# BLM_Badge_rev_B.net
KiCad netlist of a schematic drawn in EAGLE
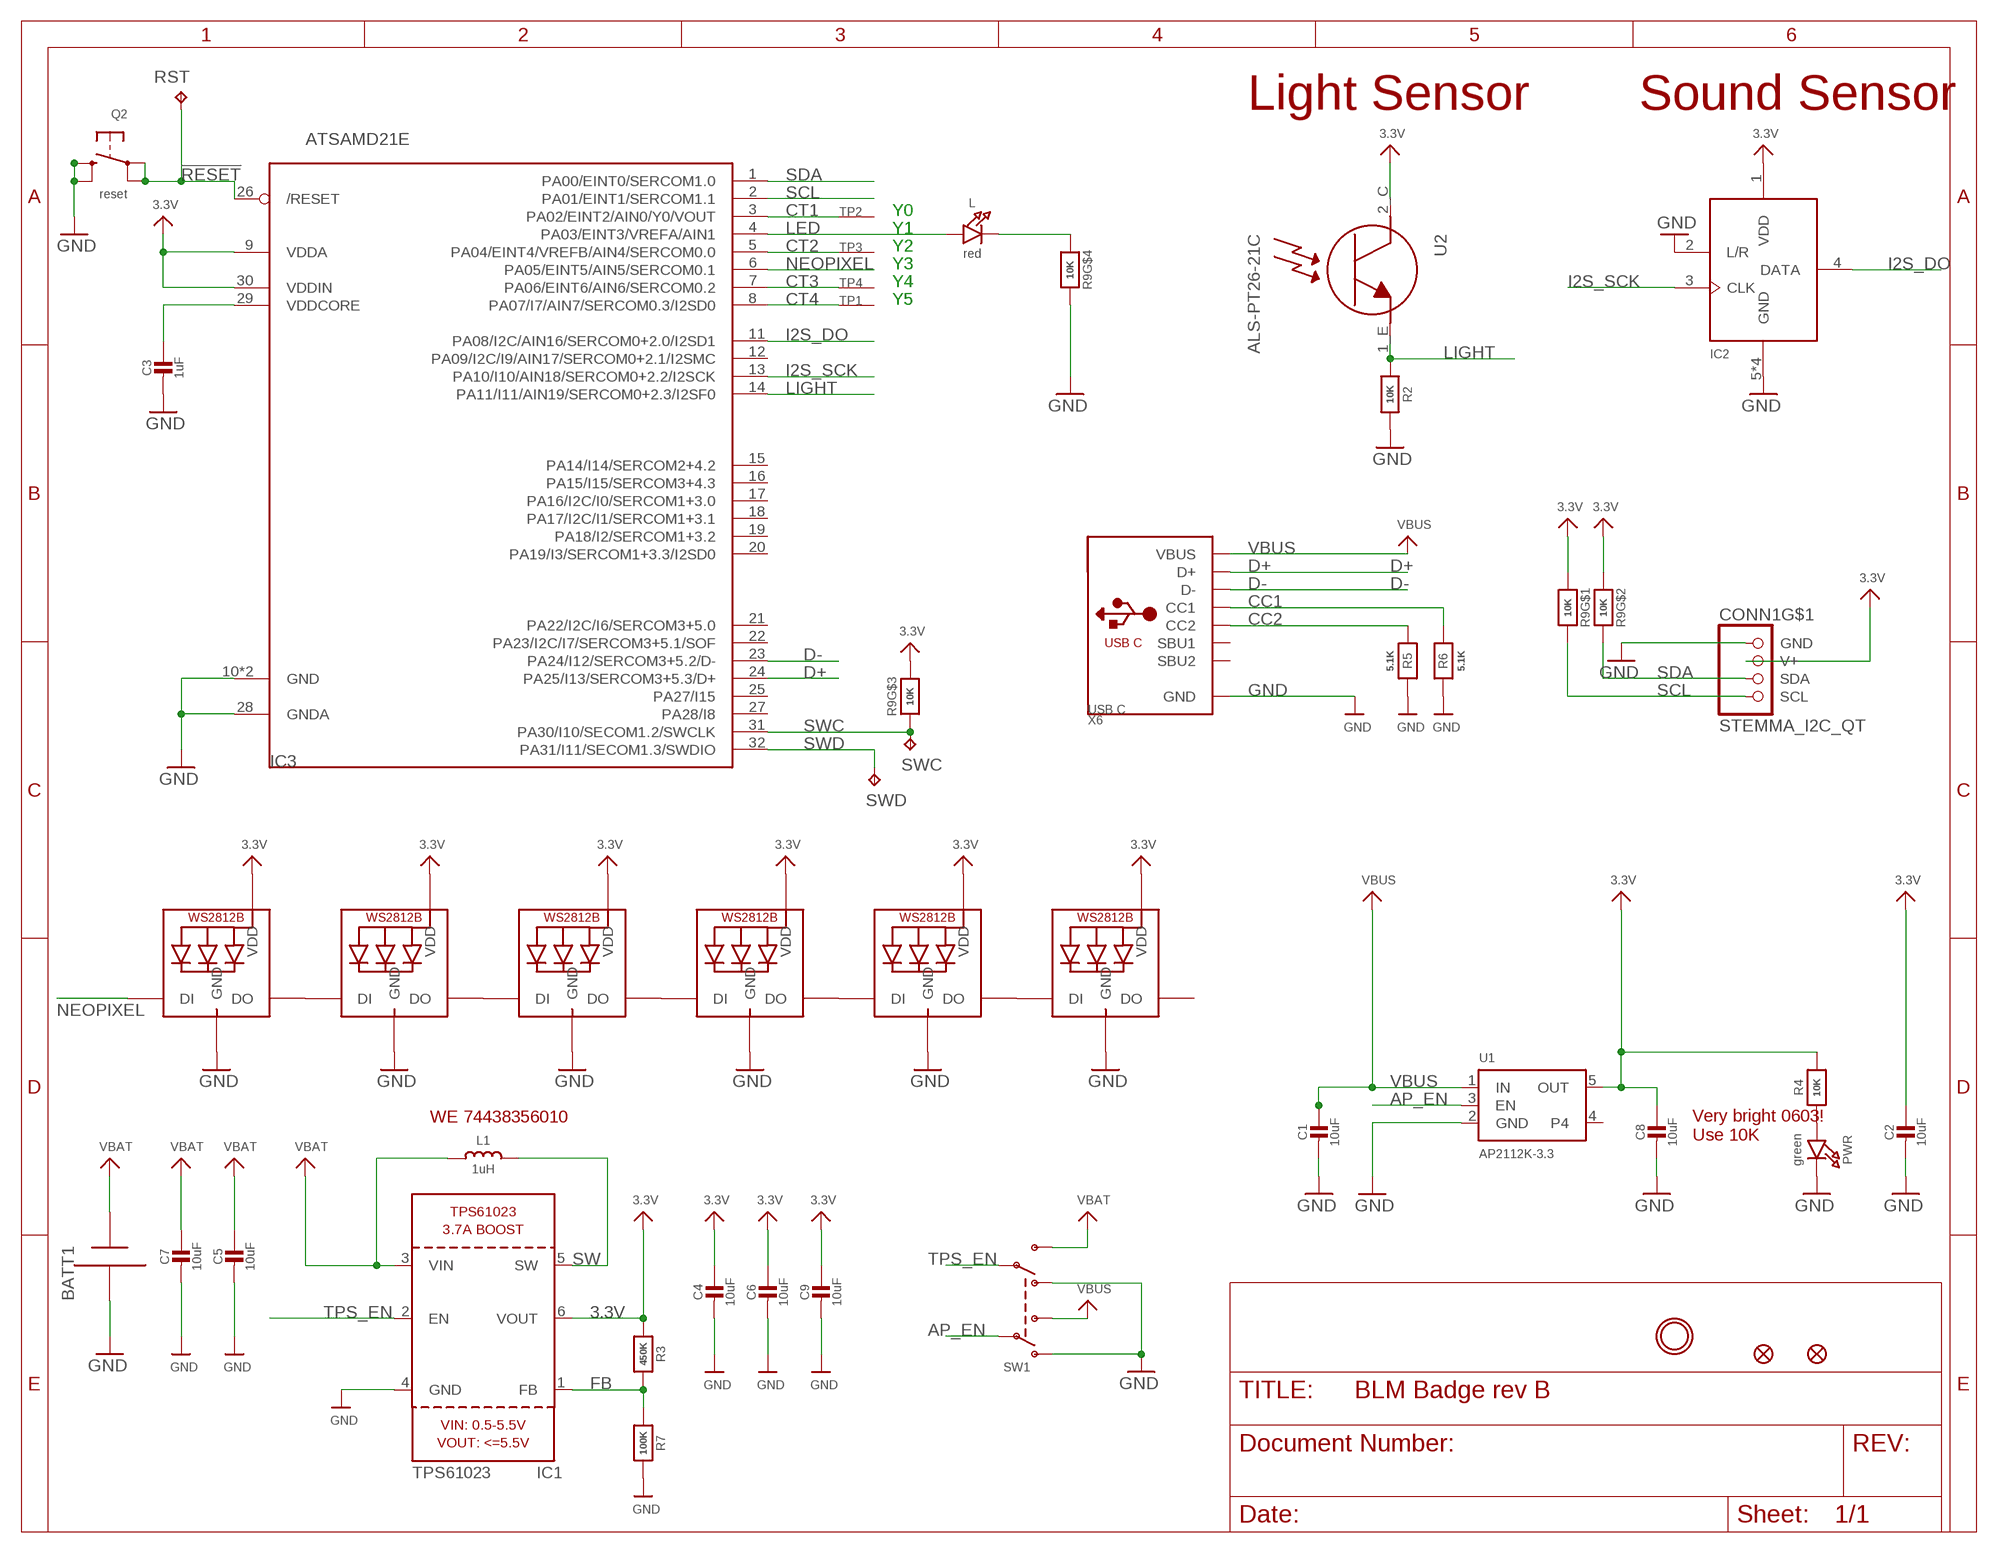
[diagram p0: schematic, sheet 1]

(export (version "E")
  (design (tool "Eeschema 10.0.6"))
  (components
    (comp (ref "BATT1")
      (value "BATTERYHOLDER_2XAAA")
      (footprint "eagle-import:2XAAA")
      (libsource (lib "eagle-import") (part "BATTERYHOLDER_2XAAA"))
    )
    (comp (ref "C1")
      (value "10uF")
      (footprint "eagle-import:0805-NO")
      (libsource (lib "eagle-import") (part "CAP_CERAMIC0805-NOOUTLINE"))
    )
    (comp (ref "C2")
      (value "10uF")
      (footprint "eagle-import:0805-NO")
      (libsource (lib "eagle-import") (part "CAP_CERAMIC0805-NOOUTLINE"))
    )
    (comp (ref "C3")
      (value "1uF")
      (footprint "eagle-import:0603-NO")
      (libsource (lib "eagle-import") (part "CAP_CERAMIC0603_NO"))
    )
    (comp (ref "C4")
      (value "10uF")
      (footprint "eagle-import:0805-NO")
      (libsource (lib "eagle-import") (part "CAP_CERAMIC0805-NOOUTLINE"))
    )
    (comp (ref "C5")
      (value "10uF")
      (footprint "eagle-import:0805-NO")
      (libsource (lib "eagle-import") (part "CAP_CERAMIC0805-NOOUTLINE"))
    )
    (comp (ref "C6")
      (value "10uF")
      (footprint "eagle-import:0805-NO")
      (libsource (lib "eagle-import") (part "CAP_CERAMIC0805-NOOUTLINE"))
    )
    (comp (ref "C7")
      (value "10uF")
      (footprint "eagle-import:0805-NO")
      (libsource (lib "eagle-import") (part "CAP_CERAMIC0805-NOOUTLINE"))
    )
    (comp (ref "C8")
      (value "10uF")
      (footprint "eagle-import:0805-NO")
      (libsource (lib "eagle-import") (part "CAP_CERAMIC0805-NOOUTLINE"))
    )
    (comp (ref "C9")
      (value "10uF")
      (footprint "eagle-import:0805-NO")
      (libsource (lib "eagle-import") (part "CAP_CERAMIC0805-NOOUTLINE"))
    )
    (comp (ref "CONN1")
      (value "STEMMA_I2C_QT")
      (footprint "eagle-import:JST_SH4")
      (libsource (lib "eagle-import") (part "STEMMA_I2C_QT"))
    )
    (comp (ref "FID1")
      (value "FIDUCIAL_1MM")
      (footprint "eagle-import:FIDUCIAL_1MM")
      (libsource (lib "eagle-import") (part "FIDUCIAL_1MM"))
    )
    (comp (ref "FID2")
      (value "FIDUCIAL_1MM")
      (footprint "eagle-import:FIDUCIAL_1MM")
      (libsource (lib "eagle-import") (part "FIDUCIAL_1MM"))
    )
    (comp (ref "IC1")
      (value "TPS61023")
      (footprint "eagle-import:SOT563")
      (libsource (lib "eagle-import") (part "TPS61023"))
    )
    (comp (ref "IC2")
      (value "MIC_PDM")
      (footprint "eagle-import:SPK0415HM4H")
      (libsource (lib "eagle-import") (part "MIC_PDM_SPK0415"))
    )
    (comp (ref "IC3")
      (value "ATSAMD21E")
      (footprint "eagle-import:QFN32_5MM")
      (libsource (lib "eagle-import") (part "ATSAMD21E"))
    )
    (comp (ref "L")
      (value "red")
      (footprint "eagle-import:CHIPLED_0603_NOOUTLINE")
      (libsource (lib "eagle-import") (part "LED0603_NOOUTLINE"))
    )
    (comp (ref "L1")
      (value "1uH")
      (footprint "eagle-import:INDUCTOR_5X5MM_TDK_VLC5045")
      (libsource (lib "eagle-import") (part "INDUCTORTDK_VLC5045"))
    )
    (comp (ref "LED2")
      (value "WS2812B_4020")
      (footprint "eagle-import:WS2812B_4020")
      (libsource (lib "eagle-import") (part "WS2812B_4020"))
    )
    (comp (ref "LED3")
      (value "WS2812B_4020")
      (footprint "eagle-import:WS2812B_4020")
      (libsource (lib "eagle-import") (part "WS2812B_4020"))
    )
    (comp (ref "LED4")
      (value "WS2812B_4020")
      (footprint "eagle-import:WS2812B_4020")
      (libsource (lib "eagle-import") (part "WS2812B_4020"))
    )
    (comp (ref "LED5")
      (value "WS2812B_4020")
      (footprint "eagle-import:WS2812B_4020")
      (libsource (lib "eagle-import") (part "WS2812B_4020"))
    )
    (comp (ref "LED6")
      (value "WS2812B_4020")
      (footprint "eagle-import:WS2812B_4020")
      (libsource (lib "eagle-import") (part "WS2812B_4020"))
    )
    (comp (ref "LED7")
      (value "WS2812B_4020")
      (footprint "eagle-import:WS2812B_4020")
      (libsource (lib "eagle-import") (part "WS2812B_4020"))
    )
    (comp (ref "PWR")
      (value "green")
      (footprint "eagle-import:CHIPLED_0603_NOOUTLINE")
      (libsource (lib "eagle-import") (part "LED0603_NOOUTLINE"))
    )
    (comp (ref "Q2")
      (value "reset")
      (footprint "eagle-import:BTN_KMR2_4.6X2.8")
      (libsource (lib "eagle-import") (part "SWITCH_TACT_SMT4.6X2.8"))
    )
    (comp (ref "R2")
      (value "10K")
      (footprint "eagle-import:0603-NO")
      (libsource (lib "eagle-import") (part "RESISTOR_0603_NOOUT"))
    )
    (comp (ref "R3")
      (value "450K")
      (footprint "eagle-import:0603-NO")
      (libsource (lib "eagle-import") (part "RESISTOR_0603_NOOUT"))
    )
    (comp (ref "R4")
      (value "10K")
      (footprint "eagle-import:0603-NO")
      (libsource (lib "eagle-import") (part "RESISTOR_0603_NOOUT"))
    )
    (comp (ref "R5")
      (value "5.1K")
      (footprint "eagle-import:0603-NO")
      (libsource (lib "eagle-import") (part "RESISTOR_0603_NOOUT"))
    )
    (comp (ref "R6")
      (value "5.1K")
      (footprint "eagle-import:0603-NO")
      (libsource (lib "eagle-import") (part "RESISTOR_0603_NOOUT"))
    )
    (comp (ref "R7")
      (value "100K")
      (footprint "eagle-import:0603-NO")
      (libsource (lib "eagle-import") (part "RESISTOR_0603_NOOUT"))
    )
    (comp (ref "R9")
      (value "10K")
      (footprint "eagle-import:RESPACK_4X0603")
      (libsource (lib "eagle-import") (part "RESISTOR_4PACK"))
    )
    (comp (ref "RST")
      (value "TPTP17R")
      (footprint "eagle-import:TP17R")
      (libsource (lib "eagle-import") (part "TPTP17R"))
    )
    (comp (ref "SW1")
      (value "SWITCH_DPDTEG1390")
      (footprint "eagle-import:EG1390")
      (libsource (lib "eagle-import") (part "SWITCH_DPDTEG1390"))
    )
    (comp (ref "SWC")
      (value "TPTP17R")
      (footprint "eagle-import:TP17R")
      (libsource (lib "eagle-import") (part "TPTP17R"))
    )
    (comp (ref "SWD")
      (value "TPTP17R")
      (footprint "eagle-import:TP17R")
      (libsource (lib "eagle-import") (part "TPTP17R"))
    )
    (comp (ref "TP1")
      (value "SEWTAPPCB_ALLIGATOR")
      (footprint "eagle-import:PCB_ALLI")
      (libsource (lib "eagle-import") (part "SEWTAPPCB_ALLIGATOR"))
    )
    (comp (ref "TP2")
      (value "SEWTAPPCB_ALLIGATOR")
      (footprint "eagle-import:PCB_ALLI")
      (libsource (lib "eagle-import") (part "SEWTAPPCB_ALLIGATOR"))
    )
    (comp (ref "TP3")
      (value "SEWTAPPCB_ALLIGATOR")
      (footprint "eagle-import:PCB_ALLI")
      (libsource (lib "eagle-import") (part "SEWTAPPCB_ALLIGATOR"))
    )
    (comp (ref "TP4")
      (value "SEWTAPPCB_ALLIGATOR")
      (footprint "eagle-import:PCB_ALLI")
      (libsource (lib "eagle-import") (part "SEWTAPPCB_ALLIGATOR"))
    )
    (comp (ref "U$33")
      (value "MOUNTINGHOLE3.0THIN")
      (footprint "eagle-import:MOUNTINGHOLE_3.0_PLATEDTHIN")
      (libsource (lib "eagle-import") (part "MOUNTINGHOLE3.0THIN"))
    )
    (comp (ref "U1")
      (value "AP2112K-3.3")
      (footprint "eagle-import:SOT23-5")
      (libsource (lib "eagle-import") (part "VREG_SOT23-5"))
    )
    (comp (ref "U2")
      (value "ALS-PT26-21C")
      (footprint "eagle-import:ALS-PT26-21C")
      (libsource (lib "eagle-import") (part "PHOTOTRANSISTOR_PT26-21C"))
    )
    (comp (ref "X6")
      (value "USB C")
      (footprint "eagle-import:USB_C_CUSB31-CFM2AX-01-X")
      (libsource (lib "eagle-import") (part "USB_C"))
    )
  )
  (nets
    (net (code "1") (name "/AP_EN") (class "Default")
      (node (ref "SW1") (pin "P1") (pinfunction "P1_P1") (pintype "passive"))
      (node (ref "U1") (pin "3") (pinfunction "EN_3") (pintype "input"))
    )
    (net (code "2") (name "/CC1") (class "Default")
      (node (ref "R6") (pin "2") (pinfunction "2_2") (pintype "passive"))
      (node (ref "X6") (pin "A5") (pinfunction "CC1_A5") (pintype "bidirectional"))
    )
    (net (code "3") (name "/CC2") (class "Default")
      (node (ref "R5") (pin "2") (pinfunction "2_2") (pintype "passive"))
      (node (ref "X6") (pin "B5") (pinfunction "CC2_B5") (pintype "bidirectional"))
    )
    (net (code "4") (name "/CT1") (class "Default")
      (node (ref "IC3") (pin "3") (pinfunction "PA02/EINT2/AIN0/Y0/VOUT_3") (pintype "bidirectional"))
      (node (ref "TP2") (pin "P$1") (pinfunction "SEW_P$1") (pintype "bidirectional"))
    )
    (net (code "5") (name "/CT2") (class "Default")
      (node (ref "IC3") (pin "5") (pinfunction "PA04/EINT4/VREFB/AIN4/SERCOM0.0_5") (pintype "bidirectional"))
      (node (ref "TP3") (pin "P$1") (pinfunction "SEW_P$1") (pintype "bidirectional"))
    )
    (net (code "6") (name "/CT3") (class "Default")
      (node (ref "IC3") (pin "7") (pinfunction "PA06/EINT6/AIN6/SERCOM0.2_7") (pintype "bidirectional"))
      (node (ref "TP4") (pin "P$1") (pinfunction "SEW_P$1") (pintype "bidirectional"))
    )
    (net (code "7") (name "/CT4") (class "Default")
      (node (ref "IC3") (pin "8") (pinfunction "PA07/I7/AIN7/SERCOM0.3/I2SD0_8") (pintype "bidirectional"))
      (node (ref "TP1") (pin "P$1") (pinfunction "SEW_P$1") (pintype "bidirectional"))
    )
    (net (code "8") (name "/D+") (class "Default")
      (node (ref "IC3") (pin "24") (pinfunction "PA25/I13/SERCOM3+5.3/D+_24") (pintype "bidirectional"))
      (node (ref "X6") (pin "A6") (pinfunction "D+_A6") (pintype "bidirectional"))
      (node (ref "X6") (pin "B6") (pinfunction "D+_B6") (pintype "bidirectional"))
    )
    (net (code "9") (name "/D-") (class "Default")
      (node (ref "IC3") (pin "23") (pinfunction "PA24/I12/SERCOM3+5.2/D-_23") (pintype "bidirectional"))
      (node (ref "X6") (pin "A7") (pinfunction "D-_A7") (pintype "bidirectional"))
      (node (ref "X6") (pin "B7") (pinfunction "D-_B7") (pintype "bidirectional"))
    )
    (net (code "10") (name "/FB") (class "Default")
      (node (ref "IC1") (pin "1") (pinfunction "FB_1") (pintype "input"))
      (node (ref "R3") (pin "2") (pinfunction "2_2") (pintype "passive"))
      (node (ref "R7") (pin "1") (pinfunction "1_1") (pintype "passive"))
    )
    (net (code "11") (name "/I2S_DO") (class "Default")
      (node (ref "IC2") (pin "4") (pinfunction "DATA_4") (pintype "bidirectional"))
      (node (ref "IC3") (pin "11") (pinfunction "PA08/I2C/AIN16/SERCOM0+2.0/I2SD1_11") (pintype "bidirectional"))
    )
    (net (code "12") (name "/I2S_SCK") (class "Default")
      (node (ref "IC2") (pin "3") (pinfunction "CLK_3") (pintype "input"))
      (node (ref "IC3") (pin "13") (pinfunction "PA10/I10/AIN18/SERCOM0+2.2/I2SCK_13") (pintype "bidirectional"))
    )
    (net (code "13") (name "/LED") (class "Default")
      (node (ref "IC3") (pin "4") (pinfunction "PA03/EINT3/VREFA/AIN1_4") (pintype "bidirectional"))
      (node (ref "L") (pin "A") (pinfunction "A_A") (pintype "passive"))
    )
    (net (code "14") (name "/LIGHT") (class "Default")
      (node (ref "IC3") (pin "14") (pinfunction "PA11/I11/AIN19/SERCOM0+2.3/I2SF0_14") (pintype "bidirectional"))
      (node (ref "R2") (pin "2") (pinfunction "2_2") (pintype "passive"))
      (node (ref "U2") (pin "1_E") (pinfunction "E_1_E") (pintype "bidirectional"))
    )
    (net (code "15") (name "/NEOPIXEL") (class "Default")
      (node (ref "IC3") (pin "6") (pinfunction "PA05/EINT5/AIN5/SERCOM0.1_6") (pintype "bidirectional"))
      (node (ref "LED2") (pin "1") (pinfunction "DI_1") (pintype "input"))
    )
    (net (code "16") (name "/SCL") (class "Default")
      (node (ref "CONN1") (pin "4") (pinfunction "SCL_4") (pintype "passive"))
      (node (ref "IC3") (pin "2") (pinfunction "PA01/EINT1/SERCOM1.1_2") (pintype "bidirectional"))
      (node (ref "R9") (pin "8") (pinfunction "2_8") (pintype "passive"))
    )
    (net (code "17") (name "/SDA") (class "Default")
      (node (ref "CONN1") (pin "3") (pinfunction "SDA_3") (pintype "passive"))
      (node (ref "IC3") (pin "1") (pinfunction "PA00/EINT0/SERCOM1.0_1") (pintype "bidirectional"))
      (node (ref "R9") (pin "7") (pinfunction "2_7") (pintype "passive"))
    )
    (net (code "18") (name "/SW") (class "Default")
      (node (ref "IC1") (pin "5") (pinfunction "SW_5") (pintype "input"))
      (node (ref "L1") (pin "P$2") (pinfunction "2_P$2") (pintype "passive"))
    )
    (net (code "19") (name "/SWC") (class "Default")
      (node (ref "IC3") (pin "31") (pinfunction "PA30/I10/SECOM1.2/SWCLK_31") (pintype "bidirectional"))
      (node (ref "R9") (pin "3") (pinfunction "1_3") (pintype "passive"))
      (node (ref "SWC") (pin "TP") (pinfunction "TP_TP") (pintype "input"))
    )
    (net (code "20") (name "/SWD") (class "Default")
      (node (ref "IC3") (pin "32") (pinfunction "PA31/I11/SECOM1.3/SWDIO_32") (pintype "bidirectional"))
      (node (ref "SWD") (pin "TP") (pinfunction "TP_TP") (pintype "input"))
    )
    (net (code "21") (name "/TPS_EN") (class "Default")
      (node (ref "IC1") (pin "2") (pinfunction "EN_2") (pintype "input"))
      (node (ref "SW1") (pin "P2") (pinfunction "P2_P2") (pintype "passive"))
    )
    (net (code "22") (name "/~{RESET}") (class "Default")
      (node (ref "IC3") (pin "26") (pinfunction "/RESET_26") (pintype "bidirectional"))
      (node (ref "Q2") (pin "A") (pinfunction "P_A") (pintype "passive"))
      (node (ref "Q2") (pin "A'") (pinfunction "P1_A'") (pintype "passive"))
      (node (ref "RST") (pin "TP") (pinfunction "TP_TP") (pintype "input"))
    )
    (net (code "23") (name "3.3V") (class "Default")
      (node (ref "C2") (pin "1") (pinfunction "1_1") (pintype "passive"))
      (node (ref "C4") (pin "1") (pinfunction "1_1") (pintype "passive"))
      (node (ref "C6") (pin "1") (pinfunction "1_1") (pintype "passive"))
      (node (ref "C8") (pin "1") (pinfunction "1_1") (pintype "passive"))
      (node (ref "C9") (pin "1") (pinfunction "1_1") (pintype "passive"))
      (node (ref "CONN1") (pin "2") (pinfunction "V+_2") (pintype "passive"))
      (node (ref "IC1") (pin "6") (pinfunction "VOUT_6") (pintype "power_in"))
      (node (ref "IC2") (pin "1") (pinfunction "VDD_1") (pintype "power_in"))
      (node (ref "IC3") (pin "30") (pinfunction "VDDIN_30") (pintype "power_in"))
      (node (ref "IC3") (pin "9") (pinfunction "VDDA_9") (pintype "power_in"))
      (node (ref "LED2") (pin "2") (pinfunction "VDD_2") (pintype "power_in"))
      (node (ref "LED3") (pin "2") (pinfunction "VDD_2") (pintype "power_in"))
      (node (ref "LED4") (pin "2") (pinfunction "VDD_2") (pintype "power_in"))
      (node (ref "LED5") (pin "2") (pinfunction "VDD_2") (pintype "power_in"))
      (node (ref "LED6") (pin "2") (pinfunction "VDD_2") (pintype "power_in"))
      (node (ref "LED7") (pin "2") (pinfunction "VDD_2") (pintype "power_in"))
      (node (ref "R3") (pin "1") (pinfunction "1_1") (pintype "passive"))
      (node (ref "R4") (pin "2") (pinfunction "2_2") (pintype "passive"))
      (node (ref "R9") (pin "1") (pinfunction "1_1") (pintype "passive"))
      (node (ref "R9") (pin "2") (pinfunction "1_2") (pintype "passive"))
      (node (ref "R9") (pin "6") (pinfunction "2_6") (pintype "passive"))
      (node (ref "U1") (pin "5") (pinfunction "OUT_5") (pintype "power_in"))
      (node (ref "U2") (pin "2_C") (pinfunction "C_2_C") (pintype "bidirectional"))
    )
    (net (code "24") (name "GND") (class "Default")
      (node (ref "BATT1") (pin "MINUS") (pinfunction "-_MINUS") (pintype "bidirectional"))
      (node (ref "C1") (pin "2") (pinfunction "2_2") (pintype "passive"))
      (node (ref "C2") (pin "2") (pinfunction "2_2") (pintype "passive"))
      (node (ref "C3") (pin "2") (pinfunction "2_2") (pintype "passive"))
      (node (ref "C4") (pin "2") (pinfunction "2_2") (pintype "passive"))
      (node (ref "C5") (pin "2") (pinfunction "2_2") (pintype "passive"))
      (node (ref "C6") (pin "2") (pinfunction "2_2") (pintype "passive"))
      (node (ref "C7") (pin "2") (pinfunction "2_2") (pintype "passive"))
      (node (ref "C8") (pin "2") (pinfunction "2_2") (pintype "passive"))
      (node (ref "C9") (pin "2") (pinfunction "2_2") (pintype "passive"))
      (node (ref "CONN1") (pin "1") (pinfunction "GND_1") (pintype "passive"))
      (node (ref "IC1") (pin "4") (pinfunction "GND_4") (pintype "power_in"))
      (node (ref "IC2") (pin "2") (pinfunction "L/R_2") (pintype "input"))
      (node (ref "IC2") (pin "5") (pinfunction "GND_5") (pintype "power_in"))
      (node (ref "IC2") (pin "6") (pinfunction "GND_6") (pintype "power_in"))
      (node (ref "IC2") (pin "7") (pinfunction "GND_7") (pintype "power_in"))
      (node (ref "IC2") (pin "8") (pinfunction "GND_8") (pintype "power_in"))
      (node (ref "IC3") (pin "10") (pinfunction "GND_10") (pintype "power_in"))
      (node (ref "IC3") (pin "28") (pinfunction "GNDA_28") (pintype "power_in"))
      (node (ref "IC3") (pin "33") (pinfunction "GND_33") (pintype "power_in"))
      (node (ref "LED2") (pin "4") (pinfunction "GND_4") (pintype "power_in"))
      (node (ref "LED3") (pin "4") (pinfunction "GND_4") (pintype "power_in"))
      (node (ref "LED4") (pin "4") (pinfunction "GND_4") (pintype "power_in"))
      (node (ref "LED5") (pin "4") (pinfunction "GND_4") (pintype "power_in"))
      (node (ref "LED6") (pin "4") (pinfunction "GND_4") (pintype "power_in"))
      (node (ref "LED7") (pin "4") (pinfunction "GND_4") (pintype "power_in"))
      (node (ref "PWR") (pin "C") (pinfunction "C_C") (pintype "passive"))
      (node (ref "Q2") (pin "B") (pinfunction "S_B") (pintype "passive"))
      (node (ref "Q2") (pin "B'") (pinfunction "S1_B'") (pintype "passive"))
      (node (ref "R2") (pin "1") (pinfunction "1_1") (pintype "passive"))
      (node (ref "R5") (pin "1") (pinfunction "1_1") (pintype "passive"))
      (node (ref "R6") (pin "1") (pinfunction "1_1") (pintype "passive"))
      (node (ref "R7") (pin "2") (pinfunction "2_2") (pintype "passive"))
      (node (ref "R9") (pin "5") (pinfunction "2_5") (pintype "passive"))
      (node (ref "SW1") (pin "O1") (pinfunction "O1_O1") (pintype "passive"))
      (node (ref "SW1") (pin "O2") (pinfunction "O2_O2") (pintype "passive"))
      (node (ref "U1") (pin "2") (pinfunction "GND_2") (pintype "power_in"))
      (node (ref "X6") (pin "A1B12") (pinfunction "GND_A1B12") (pintype "power_in"))
      (node (ref "X6") (pin "B1A12") (pinfunction "GND_B1A12") (pintype "power_in"))
    )
    (net (code "25") (name "Net-(IC3-VDDCORE)") (class "Default")
      (node (ref "C3") (pin "1") (pinfunction "1_1") (pintype "passive"))
      (node (ref "IC3") (pin "29") (pinfunction "VDDCORE_29") (pintype "power_in"))
    )
    (net (code "26") (name "Net-(LED2-DO)") (class "Default")
      (node (ref "LED2") (pin "3") (pinfunction "DO_3") (pintype "output"))
      (node (ref "LED3") (pin "1") (pinfunction "DI_1") (pintype "input"))
    )
    (net (code "27") (name "Net-(LED3-DO)") (class "Default")
      (node (ref "LED3") (pin "3") (pinfunction "DO_3") (pintype "output"))
      (node (ref "LED4") (pin "1") (pinfunction "DI_1") (pintype "input"))
    )
    (net (code "28") (name "Net-(LED4-DO)") (class "Default")
      (node (ref "LED4") (pin "3") (pinfunction "DO_3") (pintype "output"))
      (node (ref "LED5") (pin "1") (pinfunction "DI_1") (pintype "input"))
    )
    (net (code "29") (name "Net-(LED5-DO)") (class "Default")
      (node (ref "LED5") (pin "3") (pinfunction "DO_3") (pintype "output"))
      (node (ref "LED6") (pin "1") (pinfunction "DI_1") (pintype "input"))
    )
    (net (code "30") (name "Net-(LED6-DO)") (class "Default")
      (node (ref "LED6") (pin "3") (pinfunction "DO_3") (pintype "output"))
      (node (ref "LED7") (pin "1") (pinfunction "DI_1") (pintype "input"))
    )
    (net (code "31") (name "Net-(PWR-PadA)") (class "Default")
      (node (ref "PWR") (pin "A") (pinfunction "A_A") (pintype "passive"))
      (node (ref "R4") (pin "1") (pinfunction "1_1") (pintype "passive"))
    )
    (net (code "32") (name "Net-(R9D-1)") (class "Default")
      (node (ref "L") (pin "C") (pinfunction "C_C") (pintype "passive"))
      (node (ref "R9") (pin "4") (pinfunction "1_4") (pintype "passive"))
    )
    (net (code "33") (name "VBAT") (class "Default")
      (node (ref "BATT1") (pin "PLUS") (pinfunction "+_PLUS") (pintype "bidirectional"))
      (node (ref "C5") (pin "1") (pinfunction "1_1") (pintype "passive"))
      (node (ref "C7") (pin "1") (pinfunction "1_1") (pintype "passive"))
      (node (ref "IC1") (pin "3") (pinfunction "VIN_3") (pintype "power_in"))
      (node (ref "L1") (pin "P$1") (pinfunction "1_P$1") (pintype "passive"))
      (node (ref "SW1") (pin "S2") (pinfunction "S2_S2") (pintype "passive"))
    )
    (net (code "34") (name "VBUS") (class "Default")
      (node (ref "C1") (pin "1") (pinfunction "1_1") (pintype "passive"))
      (node (ref "SW1") (pin "S1") (pinfunction "S1_S1") (pintype "passive"))
      (node (ref "U1") (pin "1") (pinfunction "IN_1") (pintype "power_in"))
      (node (ref "X6") (pin "A4B9") (pinfunction "VBUS_A4B9") (pintype "power_in"))
      (node (ref "X6") (pin "B4A9") (pinfunction "VBUS_B4A9") (pintype "power_in"))
    )
    (net (code "35") (name "unconnected-(IC3-PA09{slash}I2C{slash}I9{slash}AIN17{slash}SERCOM0+2.1{slash}I2SMC-Pad12)") (class "Default")
      (node (ref "IC3") (pin "12") (pinfunction "PA09/I2C/I9/AIN17/SERCOM0+2.1/I2SMC_12") (pintype "bidirectional"))
    )
    (net (code "36") (name "unconnected-(IC3-PA14{slash}I14{slash}SERCOM2+4.2-Pad15)") (class "Default")
      (node (ref "IC3") (pin "15") (pinfunction "PA14/I14/SERCOM2+4.2_15") (pintype "bidirectional"))
    )
    (net (code "37") (name "unconnected-(IC3-PA15{slash}I15{slash}SERCOM3+4.3-Pad16)") (class "Default")
      (node (ref "IC3") (pin "16") (pinfunction "PA15/I15/SERCOM3+4.3_16") (pintype "bidirectional"))
    )
    (net (code "38") (name "unconnected-(IC3-PA16{slash}I2C{slash}I0{slash}SERCOM1+3.0-Pad17)") (class "Default")
      (node (ref "IC3") (pin "17") (pinfunction "PA16/I2C/I0/SERCOM1+3.0_17") (pintype "bidirectional"))
    )
    (net (code "39") (name "unconnected-(IC3-PA17{slash}I2C{slash}I1{slash}SERCOM1+3.1-Pad18)") (class "Default")
      (node (ref "IC3") (pin "18") (pinfunction "PA17/I2C/I1/SERCOM1+3.1_18") (pintype "bidirectional"))
    )
    (net (code "40") (name "unconnected-(IC3-PA18{slash}I2{slash}SERCOM1+3.2-Pad19)") (class "Default")
      (node (ref "IC3") (pin "19") (pinfunction "PA18/I2/SERCOM1+3.2_19") (pintype "bidirectional"))
    )
    (net (code "41") (name "unconnected-(IC3-PA19{slash}I3{slash}SERCOM1+3.3{slash}I2SD0-Pad20)") (class "Default")
      (node (ref "IC3") (pin "20") (pinfunction "PA19/I3/SERCOM1+3.3/I2SD0_20") (pintype "bidirectional"))
    )
    (net (code "42") (name "unconnected-(IC3-PA22{slash}I2C{slash}I6{slash}SERCOM3+5.0-Pad21)") (class "Default")
      (node (ref "IC3") (pin "21") (pinfunction "PA22/I2C/I6/SERCOM3+5.0_21") (pintype "bidirectional"))
    )
    (net (code "43") (name "unconnected-(IC3-PA23{slash}I2C{slash}I7{slash}SERCOM3+5.1{slash}SOF-Pad22)") (class "Default")
      (node (ref "IC3") (pin "22") (pinfunction "PA23/I2C/I7/SERCOM3+5.1/SOF_22") (pintype "bidirectional"))
    )
    (net (code "44") (name "unconnected-(IC3-PA27{slash}I15-Pad25)") (class "Default")
      (node (ref "IC3") (pin "25") (pinfunction "PA27/I15_25") (pintype "bidirectional"))
    )
    (net (code "45") (name "unconnected-(IC3-PA28{slash}I8-Pad27)") (class "Default")
      (node (ref "IC3") (pin "27") (pinfunction "PA28/I8_27") (pintype "bidirectional"))
    )
    (net (code "46") (name "unconnected-(LED7-DO-Pad3)") (class "Default")
      (node (ref "LED7") (pin "3") (pinfunction "DO_3") (pintype "output"))
    )
    (net (code "47") (name "unconnected-(U1-P4-Pad4)") (class "Default")
      (node (ref "U1") (pin "4") (pinfunction "P4_4") (pintype "bidirectional"))
    )
    (net (code "48") (name "unconnected-(X6-SBU1-PadA8)") (class "Default")
      (node (ref "X6") (pin "A8") (pinfunction "SBU1_A8") (pintype "bidirectional"))
    )
    (net (code "49") (name "unconnected-(X6-SBU2-PadB8)") (class "Default")
      (node (ref "X6") (pin "B8") (pinfunction "SBU2_B8") (pintype "bidirectional"))
    )
  )
)
